# 0-FlowSensor.net
KiCad netlist of a schematic drawn in Altium Designer
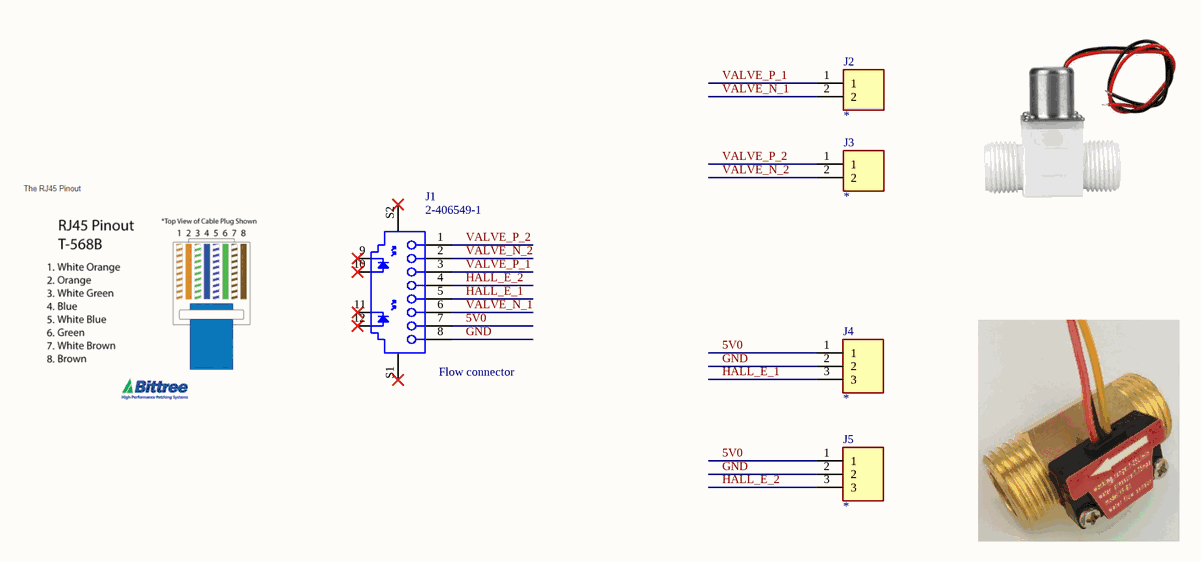
[diagram p0: 0-FlowSensor.SchDoc]

(export (version "E")
  (design (tool "Eeschema 10.0.6"))
  (components
    (comp (ref "J1")
      (value "2-406549-1")
      (footprint "TECO-2-406549-1_V")
      (description "RJ45 Connector, Pitch 1.016 mm, 8 Position, Height 14.22 mm, Tail Length 3.18 mm, RoHS, Tray")
      (fields (field (name "MANUFACTURER") "TE Connectivity"))
      (libsource (lib "Altium Content Vault") (part "RJ45-12-2SHLD_A"))
    )
    (comp (ref "J2")
      (value "282841-2")
      (footprint "TE_282841-2")
      (description "Conn Terminal Block 2 POS 5.08mm Solder ST Thru-Hole 17.5A/Contact")
      (fields (field (name "MF") "TE Connectivity") (field (name "COMMENT_1") "*"))
      (libsource (lib "PTR500-2") (part "282841-2"))
    )
    (comp (ref "J3")
      (value "282841-2")
      (footprint "TE_282841-2")
      (description "Conn Terminal Block 2 POS 5.08mm Solder ST Thru-Hole 17.5A/Contact")
      (fields (field (name "MF") "TE Connectivity") (field (name "COMMENT_1") "*"))
      (libsource (lib "PTR500-2") (part "282841-2"))
    )
    (comp (ref "J4")
      (value "282841-3")
      (footprint "TE_282841-3")
      (description "Conn Terminal Block 3 POS 5.08mm Solder ST Thru-Hole 17.5A/Contact")
      (fields
        (field (name "MF") "TE Connectivity")
        (field (name "MP") "282841-2")
        (field (name "COMMENT_1") "*")
      )
      (libsource (lib "PTR500-2") (part "282841-3"))
    )
    (comp (ref "J5")
      (value "282841-3")
      (footprint "TE_282841-3")
      (description "Conn Terminal Block 3 POS 5.08mm Solder ST Thru-Hole 17.5A/Contact")
      (fields
        (field (name "MF") "TE Connectivity")
        (field (name "MP") "282841-2")
        (field (name "COMMENT_1") "*")
      )
      (libsource (lib "PTR500-2") (part "282841-3"))
    )
  )
  (nets
    (net (code "1") (name "/5V0") (class "Default")
      (node (ref "J1") (pin "7") (pinfunction "7_7") (pintype "passive"))
      (node (ref "J4") (pin "1") (pinfunction "1_1") (pintype "passive"))
      (node (ref "J5") (pin "1") (pinfunction "1_1") (pintype "passive"))
    )
    (net (code "2") (name "/GND") (class "Default")
      (node (ref "J1") (pin "8") (pinfunction "8_8") (pintype "passive"))
      (node (ref "J4") (pin "2") (pinfunction "2_2") (pintype "passive"))
      (node (ref "J5") (pin "2") (pinfunction "2_2") (pintype "passive"))
    )
    (net (code "3") (name "/HALL_E_1") (class "Default")
      (node (ref "J1") (pin "5") (pinfunction "5_5") (pintype "passive"))
      (node (ref "J4") (pin "3") (pinfunction "3_3") (pintype "passive"))
    )
    (net (code "4") (name "/HALL_E_2") (class "Default")
      (node (ref "J1") (pin "4") (pinfunction "4_4") (pintype "passive"))
      (node (ref "J5") (pin "3") (pinfunction "3_3") (pintype "passive"))
    )
    (net (code "5") (name "/VALVE_N_1") (class "Default")
      (node (ref "J1") (pin "6") (pinfunction "6_6") (pintype "passive"))
      (node (ref "J2") (pin "2") (pinfunction "2_2") (pintype "passive"))
    )
    (net (code "6") (name "/VALVE_N_2") (class "Default")
      (node (ref "J1") (pin "2") (pinfunction "2_2") (pintype "passive"))
      (node (ref "J3") (pin "2") (pinfunction "2_2") (pintype "passive"))
    )
    (net (code "7") (name "/VALVE_P_1") (class "Default")
      (node (ref "J1") (pin "3") (pinfunction "3_3") (pintype "passive"))
      (node (ref "J2") (pin "1") (pinfunction "1_1") (pintype "passive"))
    )
    (net (code "8") (name "/VALVE_P_2") (class "Default")
      (node (ref "J1") (pin "1") (pinfunction "1_1") (pintype "passive"))
      (node (ref "J3") (pin "1") (pinfunction "1_1") (pintype "passive"))
    )
    (net (code "9") (name "unconnected-(J1-Pad9)") (class "Default")
      (node (ref "J1") (pin "9") (pinfunction "9_9") (pintype "passive+no_connect"))
    )
    (net (code "10") (name "unconnected-(J1-Pad10)") (class "Default")
      (node (ref "J1") (pin "10") (pinfunction "10_10") (pintype "passive+no_connect"))
    )
    (net (code "11") (name "unconnected-(J1-Pad11)") (class "Default")
      (node (ref "J1") (pin "11") (pinfunction "11_11") (pintype "passive+no_connect"))
    )
    (net (code "12") (name "unconnected-(J1-Pad12)") (class "Default")
      (node (ref "J1") (pin "12") (pinfunction "12_12") (pintype "passive+no_connect"))
    )
    (net (code "13") (name "unconnected-(J1-PadS1)") (class "Default")
      (node (ref "J1") (pin "S1") (pinfunction "S1_S1") (pintype "passive+no_connect"))
    )
    (net (code "14") (name "unconnected-(J1-PadS2)") (class "Default")
      (node (ref "J1") (pin "S2") (pinfunction "S2_S2") (pintype "passive+no_connect"))
    )
  )
)
